# Breakout_Board_28_pin.net
KiCad netlist of a schematic drawn in EasyEDA Pro
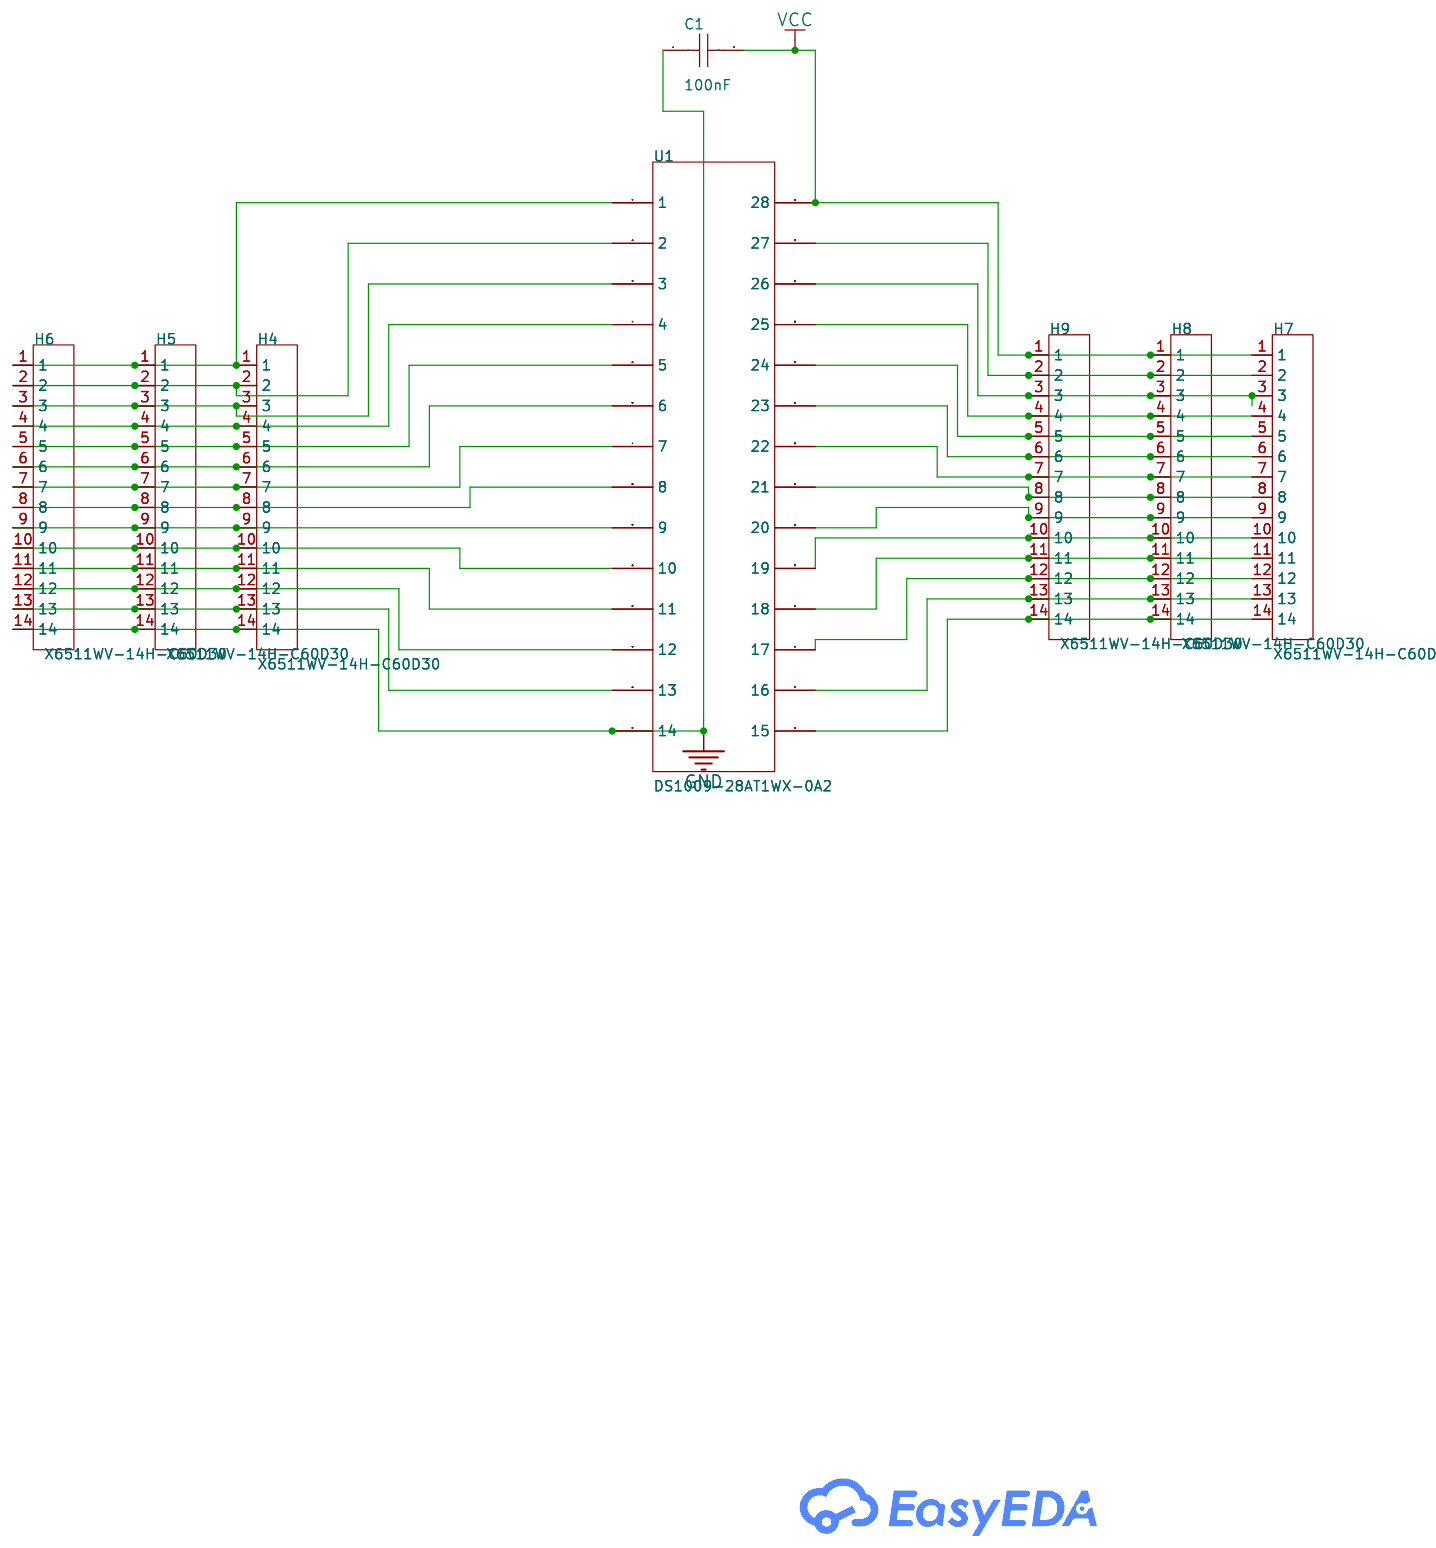
[diagram p0: schematic sheet]

(export (version "E")
  (design (tool "Eeschema 10.0.6"))
  (components
    (comp (ref "C1")
      (value "100nF")
      (footprint "easyedapro:CAP-TH_L8.5-W5.0-P5.00-D1.2")
      (fields (field (name "Manufacturer Part") "CT4-0805B104K500F3") (field (name "Manufacturer") "FH(风华)"))
      (libsource (lib "easyedapro") (part "CT4-0805B104K500F3"))
    )
    (comp (ref "H4")
      (value "X6511WV-14H-C60D30")
      (footprint "easyedapro:HDR-TH_14P-P2.54-V-M")
      (fields (field (name "Manufacturer") "XKB Connection(中国星坤)"))
      (libsource (lib "easyedapro") (part "X6511WV-14H-C30D60"))
    )
    (comp (ref "H5")
      (value "X6511WV-14H-C60D30")
      (footprint "easyedapro:HDR-TH_14P-P2.54-V-M")
      (fields (field (name "Manufacturer") "XKB Connection(中国星坤)"))
      (libsource (lib "easyedapro") (part "X6511WV-14H-C30D60"))
    )
    (comp (ref "H6")
      (value "X6511WV-14H-C60D30")
      (footprint "easyedapro:HDR-TH_14P-P2.54-V-M")
      (fields (field (name "Manufacturer") "XKB Connection(中国星坤)"))
      (libsource (lib "easyedapro") (part "X6511WV-14H-C30D60"))
    )
    (comp (ref "H7")
      (value "X6511WV-14H-C60D30")
      (footprint "easyedapro:HDR-TH_14P-P2.54-V-M")
      (fields (field (name "Manufacturer") "XKB Connection(中国星坤)"))
      (libsource (lib "easyedapro") (part "X6511WV-14H-C30D60"))
    )
    (comp (ref "H8")
      (value "X6511WV-14H-C60D30")
      (footprint "easyedapro:HDR-TH_14P-P2.54-V-M")
      (fields (field (name "Manufacturer") "XKB Connection(中国星坤)"))
      (libsource (lib "easyedapro") (part "X6511WV-14H-C30D60"))
    )
    (comp (ref "H9")
      (value "X6511WV-14H-C60D30")
      (footprint "easyedapro:HDR-TH_14P-P2.54-V-M")
      (fields (field (name "Manufacturer") "XKB Connection(中国星坤)"))
      (libsource (lib "easyedapro") (part "X6511WV-14H-C30D60"))
    )
    (comp (ref "U1")
      (value "DS1009-28AT1WX-0A2")
      (footprint "easyedapro:DIP-28_L35.6-W17.8-P2.54-LS15.2-BL")
      (fields (field (name "Manufacturer") "CONNFLY"))
      (libsource (lib "easyedapro") (part "DS1009-28AT1WX-0A2"))
    )
  )
  (nets
    (net (code "1") (name "GND") (class "Default")
      (node (ref "C1") (pin "1") (pinfunction "1_1") (pintype "unspecified"))
      (node (ref "H4") (pin "14") (pinfunction "14_14") (pintype "unspecified"))
      (node (ref "H5") (pin "14") (pinfunction "14_14") (pintype "unspecified"))
      (node (ref "H6") (pin "14") (pinfunction "14_14") (pintype "unspecified"))
      (node (ref "U1") (pin "14") (pinfunction "14_14") (pintype "input"))
    )
    (net (code "2") (name "Net-(H4-Pad1)") (class "Default")
      (node (ref "H4") (pin "1") (pinfunction "1_1") (pintype "unspecified"))
      (node (ref "H5") (pin "1") (pinfunction "1_1") (pintype "unspecified"))
      (node (ref "H6") (pin "1") (pinfunction "1_1") (pintype "unspecified"))
      (node (ref "U1") (pin "1") (pinfunction "1_1") (pintype "input"))
    )
    (net (code "3") (name "Net-(H4-Pad2)") (class "Default")
      (node (ref "H4") (pin "2") (pinfunction "2_2") (pintype "unspecified"))
      (node (ref "H5") (pin "2") (pinfunction "2_2") (pintype "unspecified"))
      (node (ref "H6") (pin "2") (pinfunction "2_2") (pintype "unspecified"))
      (node (ref "U1") (pin "2") (pinfunction "2_2") (pintype "input"))
    )
    (net (code "4") (name "Net-(H4-Pad3)") (class "Default")
      (node (ref "H4") (pin "3") (pinfunction "3_3") (pintype "unspecified"))
      (node (ref "H5") (pin "3") (pinfunction "3_3") (pintype "unspecified"))
      (node (ref "H6") (pin "3") (pinfunction "3_3") (pintype "unspecified"))
      (node (ref "U1") (pin "3") (pinfunction "3_3") (pintype "input"))
    )
    (net (code "5") (name "Net-(H4-Pad4)") (class "Default")
      (node (ref "H4") (pin "4") (pinfunction "4_4") (pintype "unspecified"))
      (node (ref "H5") (pin "4") (pinfunction "4_4") (pintype "unspecified"))
      (node (ref "H6") (pin "4") (pinfunction "4_4") (pintype "unspecified"))
      (node (ref "U1") (pin "4") (pinfunction "4_4") (pintype "input"))
    )
    (net (code "6") (name "Net-(H4-Pad5)") (class "Default")
      (node (ref "H4") (pin "5") (pinfunction "5_5") (pintype "unspecified"))
      (node (ref "H5") (pin "5") (pinfunction "5_5") (pintype "unspecified"))
      (node (ref "H6") (pin "5") (pinfunction "5_5") (pintype "unspecified"))
      (node (ref "U1") (pin "5") (pinfunction "5_5") (pintype "input"))
    )
    (net (code "7") (name "Net-(H4-Pad6)") (class "Default")
      (node (ref "H4") (pin "6") (pinfunction "6_6") (pintype "unspecified"))
      (node (ref "H5") (pin "6") (pinfunction "6_6") (pintype "unspecified"))
      (node (ref "H6") (pin "6") (pinfunction "6_6") (pintype "unspecified"))
      (node (ref "U1") (pin "6") (pinfunction "6_6") (pintype "input"))
    )
    (net (code "8") (name "Net-(H4-Pad7)") (class "Default")
      (node (ref "H4") (pin "7") (pinfunction "7_7") (pintype "unspecified"))
      (node (ref "H5") (pin "7") (pinfunction "7_7") (pintype "unspecified"))
      (node (ref "H6") (pin "7") (pinfunction "7_7") (pintype "unspecified"))
      (node (ref "U1") (pin "7") (pinfunction "7_7") (pintype "input"))
    )
    (net (code "9") (name "Net-(H4-Pad8)") (class "Default")
      (node (ref "H4") (pin "8") (pinfunction "8_8") (pintype "unspecified"))
      (node (ref "H5") (pin "8") (pinfunction "8_8") (pintype "unspecified"))
      (node (ref "H6") (pin "8") (pinfunction "8_8") (pintype "unspecified"))
      (node (ref "U1") (pin "8") (pinfunction "8_8") (pintype "input"))
    )
    (net (code "10") (name "Net-(H4-Pad9)") (class "Default")
      (node (ref "H4") (pin "9") (pinfunction "9_9") (pintype "unspecified"))
      (node (ref "H5") (pin "9") (pinfunction "9_9") (pintype "unspecified"))
      (node (ref "H6") (pin "9") (pinfunction "9_9") (pintype "unspecified"))
      (node (ref "U1") (pin "9") (pinfunction "9_9") (pintype "input"))
    )
    (net (code "11") (name "Net-(H4-Pad10)") (class "Default")
      (node (ref "H4") (pin "10") (pinfunction "10_10") (pintype "unspecified"))
      (node (ref "H5") (pin "10") (pinfunction "10_10") (pintype "unspecified"))
      (node (ref "H6") (pin "10") (pinfunction "10_10") (pintype "unspecified"))
      (node (ref "U1") (pin "10") (pinfunction "10_10") (pintype "input"))
    )
    (net (code "12") (name "Net-(H4-Pad11)") (class "Default")
      (node (ref "H4") (pin "11") (pinfunction "11_11") (pintype "unspecified"))
      (node (ref "H5") (pin "11") (pinfunction "11_11") (pintype "unspecified"))
      (node (ref "H6") (pin "11") (pinfunction "11_11") (pintype "unspecified"))
      (node (ref "U1") (pin "11") (pinfunction "11_11") (pintype "input"))
    )
    (net (code "13") (name "Net-(H4-Pad12)") (class "Default")
      (node (ref "H4") (pin "12") (pinfunction "12_12") (pintype "unspecified"))
      (node (ref "H5") (pin "12") (pinfunction "12_12") (pintype "unspecified"))
      (node (ref "H6") (pin "12") (pinfunction "12_12") (pintype "unspecified"))
      (node (ref "U1") (pin "12") (pinfunction "12_12") (pintype "input"))
    )
    (net (code "14") (name "Net-(H4-Pad13)") (class "Default")
      (node (ref "H4") (pin "13") (pinfunction "13_13") (pintype "unspecified"))
      (node (ref "H5") (pin "13") (pinfunction "13_13") (pintype "unspecified"))
      (node (ref "H6") (pin "13") (pinfunction "13_13") (pintype "unspecified"))
      (node (ref "U1") (pin "13") (pinfunction "13_13") (pintype "input"))
    )
    (net (code "15") (name "Net-(H7-Pad2)") (class "Default")
      (node (ref "H7") (pin "2") (pinfunction "2_2") (pintype "unspecified"))
      (node (ref "H8") (pin "2") (pinfunction "2_2") (pintype "unspecified"))
      (node (ref "H9") (pin "2") (pinfunction "2_2") (pintype "unspecified"))
      (node (ref "U1") (pin "27") (pinfunction "27_27") (pintype "input"))
    )
    (net (code "16") (name "Net-(H7-Pad3)") (class "Default")
      (node (ref "H7") (pin "3") (pinfunction "3_3") (pintype "unspecified"))
      (node (ref "H8") (pin "3") (pinfunction "3_3") (pintype "unspecified"))
      (node (ref "H9") (pin "3") (pinfunction "3_3") (pintype "unspecified"))
      (node (ref "U1") (pin "26") (pinfunction "26_26") (pintype "input"))
    )
    (net (code "17") (name "Net-(H7-Pad4)") (class "Default")
      (node (ref "H7") (pin "4") (pinfunction "4_4") (pintype "unspecified"))
      (node (ref "H8") (pin "4") (pinfunction "4_4") (pintype "unspecified"))
      (node (ref "H9") (pin "4") (pinfunction "4_4") (pintype "unspecified"))
      (node (ref "U1") (pin "25") (pinfunction "25_25") (pintype "input"))
    )
    (net (code "18") (name "Net-(H7-Pad5)") (class "Default")
      (node (ref "H7") (pin "5") (pinfunction "5_5") (pintype "unspecified"))
      (node (ref "H8") (pin "5") (pinfunction "5_5") (pintype "unspecified"))
      (node (ref "H9") (pin "5") (pinfunction "5_5") (pintype "unspecified"))
      (node (ref "U1") (pin "24") (pinfunction "24_24") (pintype "input"))
    )
    (net (code "19") (name "Net-(H7-Pad6)") (class "Default")
      (node (ref "H7") (pin "6") (pinfunction "6_6") (pintype "unspecified"))
      (node (ref "H8") (pin "6") (pinfunction "6_6") (pintype "unspecified"))
      (node (ref "H9") (pin "6") (pinfunction "6_6") (pintype "unspecified"))
      (node (ref "U1") (pin "23") (pinfunction "23_23") (pintype "input"))
    )
    (net (code "20") (name "Net-(H7-Pad7)") (class "Default")
      (node (ref "H7") (pin "7") (pinfunction "7_7") (pintype "unspecified"))
      (node (ref "H8") (pin "7") (pinfunction "7_7") (pintype "unspecified"))
      (node (ref "H9") (pin "7") (pinfunction "7_7") (pintype "unspecified"))
      (node (ref "U1") (pin "22") (pinfunction "22_22") (pintype "input"))
    )
    (net (code "21") (name "Net-(H7-Pad8)") (class "Default")
      (node (ref "H7") (pin "8") (pinfunction "8_8") (pintype "unspecified"))
      (node (ref "H8") (pin "8") (pinfunction "8_8") (pintype "unspecified"))
      (node (ref "H9") (pin "8") (pinfunction "8_8") (pintype "unspecified"))
      (node (ref "U1") (pin "21") (pinfunction "21_21") (pintype "input"))
    )
    (net (code "22") (name "Net-(H7-Pad9)") (class "Default")
      (node (ref "H7") (pin "9") (pinfunction "9_9") (pintype "unspecified"))
      (node (ref "H8") (pin "9") (pinfunction "9_9") (pintype "unspecified"))
      (node (ref "H9") (pin "9") (pinfunction "9_9") (pintype "unspecified"))
      (node (ref "U1") (pin "20") (pinfunction "20_20") (pintype "input"))
    )
    (net (code "23") (name "Net-(H7-Pad10)") (class "Default")
      (node (ref "H7") (pin "10") (pinfunction "10_10") (pintype "unspecified"))
      (node (ref "H8") (pin "10") (pinfunction "10_10") (pintype "unspecified"))
      (node (ref "H9") (pin "10") (pinfunction "10_10") (pintype "unspecified"))
      (node (ref "U1") (pin "19") (pinfunction "19_19") (pintype "input"))
    )
    (net (code "24") (name "Net-(H7-Pad11)") (class "Default")
      (node (ref "H7") (pin "11") (pinfunction "11_11") (pintype "unspecified"))
      (node (ref "H8") (pin "11") (pinfunction "11_11") (pintype "unspecified"))
      (node (ref "H9") (pin "11") (pinfunction "11_11") (pintype "unspecified"))
      (node (ref "U1") (pin "18") (pinfunction "18_18") (pintype "input"))
    )
    (net (code "25") (name "Net-(H7-Pad12)") (class "Default")
      (node (ref "H7") (pin "12") (pinfunction "12_12") (pintype "unspecified"))
      (node (ref "H8") (pin "12") (pinfunction "12_12") (pintype "unspecified"))
      (node (ref "H9") (pin "12") (pinfunction "12_12") (pintype "unspecified"))
      (node (ref "U1") (pin "17") (pinfunction "17_17") (pintype "input"))
    )
    (net (code "26") (name "Net-(H7-Pad13)") (class "Default")
      (node (ref "H7") (pin "13") (pinfunction "13_13") (pintype "unspecified"))
      (node (ref "H8") (pin "13") (pinfunction "13_13") (pintype "unspecified"))
      (node (ref "H9") (pin "13") (pinfunction "13_13") (pintype "unspecified"))
      (node (ref "U1") (pin "16") (pinfunction "16_16") (pintype "input"))
    )
    (net (code "27") (name "Net-(H7-Pad14)") (class "Default")
      (node (ref "H7") (pin "14") (pinfunction "14_14") (pintype "unspecified"))
      (node (ref "H8") (pin "14") (pinfunction "14_14") (pintype "unspecified"))
      (node (ref "H9") (pin "14") (pinfunction "14_14") (pintype "unspecified"))
      (node (ref "U1") (pin "15") (pinfunction "15_15") (pintype "input"))
    )
    (net (code "28") (name "VCC") (class "Default")
      (node (ref "C1") (pin "2") (pinfunction "2_2") (pintype "unspecified"))
      (node (ref "H7") (pin "1") (pinfunction "1_1") (pintype "unspecified"))
      (node (ref "H8") (pin "1") (pinfunction "1_1") (pintype "unspecified"))
      (node (ref "H9") (pin "1") (pinfunction "1_1") (pintype "unspecified"))
      (node (ref "U1") (pin "28") (pinfunction "28_28") (pintype "input"))
    )
  )
)
